# node.net
KiCad netlist of a schematic drawn in EAGLE
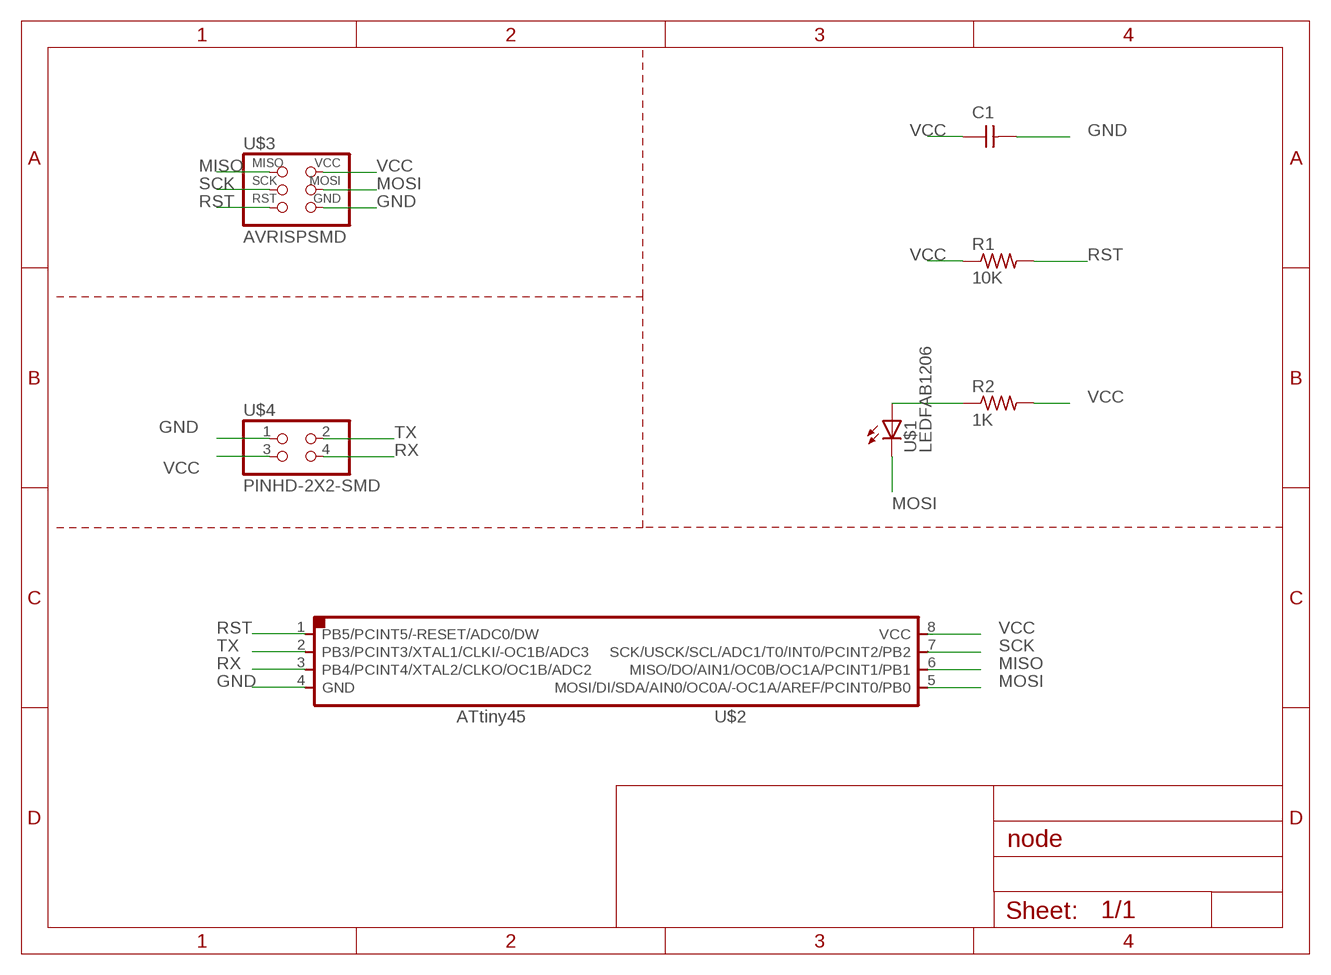
[diagram p0: schematic, sheet 1]

(export (version "E")
  (design (tool "Eeschema 10.0.6"))
  (components
    (comp (ref "C1")
      (value "CAP-UNPOLARIZED")
      (footprint "eagle-import:C1206")
      (libsource (lib "eagle-import") (part "CAP-UNPOLARIZED"))
    )
    (comp (ref "R1")
      (value "10K")
      (footprint "eagle-import:R1206FAB")
      (libsource (lib "eagle-import") (part "RES-US1206FAB"))
    )
    (comp (ref "R2")
      (value "1K")
      (footprint "eagle-import:R1206FAB")
      (libsource (lib "eagle-import") (part "RES-US1206FAB"))
    )
    (comp (ref "U$1")
      (value "LEDFAB1206")
      (footprint "eagle-import:LED1206FAB")
      (libsource (lib "eagle-import") (part "LEDFAB1206"))
    )
    (comp (ref "U$2")
      (value "ATTINY45SI")
      (footprint "eagle-import:SOIC8")
      (libsource (lib "eagle-import") (part "ATTINY45SI"))
    )
    (comp (ref "U$3")
      (value "AVRISPSMD")
      (footprint "eagle-import:2X03SMD")
      (libsource (lib "eagle-import") (part "AVRISPSMD"))
    )
    (comp (ref "U$4")
      (value "PINHD-2X2-SMD")
      (footprint "eagle-import:2X02SMD")
      (libsource (lib "eagle-import") (part "PINHD-2X2-SMD"))
    )
  )
  (nets
    (net (code "1") (name "/GND") (class "Default")
      (node (ref "C1") (pin "2") (pinfunction "2_2") (pintype "passive"))
      (node (ref "U$2") (pin "4") (pinfunction "GND_4") (pintype "bidirectional"))
      (node (ref "U$3") (pin "6") (pinfunction "GND_6") (pintype "passive"))
      (node (ref "U$4") (pin "1") (pinfunction "1_1") (pintype "passive"))
    )
    (net (code "2") (name "/MISO") (class "Default")
      (node (ref "U$2") (pin "6") (pinfunction "MISO/DO/AIN1/OC0B/OC1A/PCINT1/PB1_6") (pintype "bidirectional"))
      (node (ref "U$3") (pin "1") (pinfunction "MISO_1") (pintype "passive"))
    )
    (net (code "3") (name "/MOSI") (class "Default")
      (node (ref "U$1") (pin "2") (pinfunction "C_2") (pintype "passive"))
      (node (ref "U$2") (pin "5") (pinfunction "MOSI/DI/SDA/AIN0/OC0A/-OC1A/AREF/PCINT0/PB0_5") (pintype "bidirectional"))
      (node (ref "U$3") (pin "4") (pinfunction "MOSI_4") (pintype "passive"))
    )
    (net (code "4") (name "/RST") (class "Default")
      (node (ref "R1") (pin "2") (pinfunction "2_2") (pintype "passive"))
      (node (ref "U$2") (pin "1") (pinfunction "PB5/PCINT5/-RESET/ADC0/DW_1") (pintype "bidirectional"))
      (node (ref "U$3") (pin "5") (pinfunction "RST_5") (pintype "passive"))
    )
    (net (code "5") (name "/RX") (class "Default")
      (node (ref "U$2") (pin "3") (pinfunction "PB4/PCINT4/XTAL2/CLKO/OC1B/ADC2_3") (pintype "bidirectional"))
      (node (ref "U$4") (pin "4") (pinfunction "4_4") (pintype "passive"))
    )
    (net (code "6") (name "/SCK") (class "Default")
      (node (ref "U$2") (pin "7") (pinfunction "SCK/USCK/SCL/ADC1/T0/INT0/PCINT2/PB2_7") (pintype "bidirectional"))
      (node (ref "U$3") (pin "3") (pinfunction "SCK_3") (pintype "passive"))
    )
    (net (code "7") (name "/TX") (class "Default")
      (node (ref "U$2") (pin "2") (pinfunction "PB3/PCINT3/XTAL1/CLKI/-OC1B/ADC3_2") (pintype "bidirectional"))
      (node (ref "U$4") (pin "2") (pinfunction "2_2") (pintype "passive"))
    )
    (net (code "8") (name "/VCC") (class "Default")
      (node (ref "C1") (pin "1") (pinfunction "1_1") (pintype "passive"))
      (node (ref "R1") (pin "1") (pinfunction "1_1") (pintype "passive"))
      (node (ref "R2") (pin "2") (pinfunction "2_2") (pintype "passive"))
      (node (ref "U$2") (pin "8") (pinfunction "VCC_8") (pintype "bidirectional"))
      (node (ref "U$3") (pin "2") (pinfunction "VCC_2") (pintype "passive"))
      (node (ref "U$4") (pin "3") (pinfunction "3_3") (pintype "passive"))
    )
    (net (code "9") (name "Net-(U$1-A)") (class "Default")
      (node (ref "R2") (pin "1") (pinfunction "1_1") (pintype "passive"))
      (node (ref "U$1") (pin "1") (pinfunction "A_1") (pintype "passive"))
    )
  )
)
